# MCU.net
KiCad netlist of a schematic drawn in Altium Designer
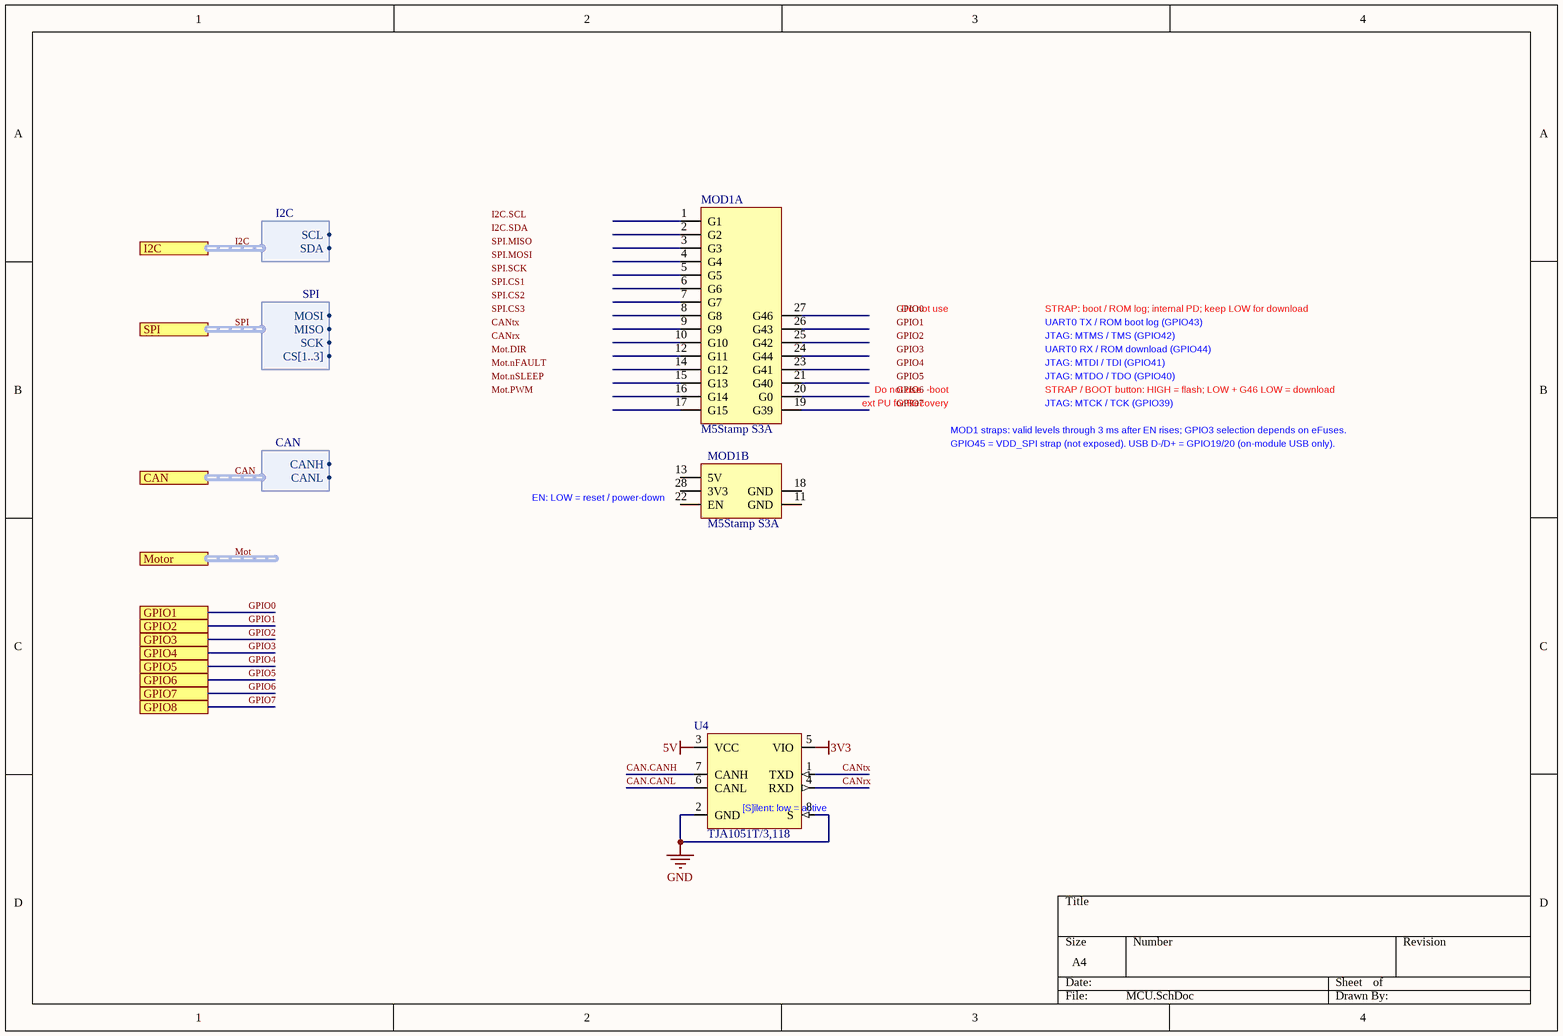
[diagram p0: MCU.SchDoc]

(export (version "E")
  (design (tool "Eeschema 10.0.6"))
  (components
    (comp (ref "MOD1")
      (value "M5Stamp S3A")
      (footprint "M5Stamp S3A-mfg")
      (description "ESP32-S3FN8, 8MB Flash, RGB LED")
      (libsource (lib "AFR365") (part "M5Stamp_S3A"))
    )
    (comp (ref "U4")
      (value "TJA1051T/3,118")
      (footprint "NXP-SOIC-8_L")
      (description "Interface Circuit, 1-Trnsvr, PDSO8")
      (libsource (lib "AFR365") (part "NXP-TJA1051T_3-SOIC-8"))
    )
  )
  (nets
    (net (code "5") (name "/CAN.CANH") (class "Default")
      (node (ref "U4") (pin "7") (pinfunction "CANH_7") (pintype "passive"))
    )
    (net (code "6") (name "/CAN.CANL") (class "Default")
      (node (ref "U4") (pin "6") (pinfunction "CANL_6") (pintype "passive"))
    )
    (net (code "7") (name "/CANrx") (class "Default")
      (node (ref "U4") (pin "4") (pinfunction "RXD_4") (pintype "output"))
    )
    (net (code "8") (name "/CANtx") (class "Default")
      (node (ref "U4") (pin "1") (pinfunction "TXD_1") (pintype "input"))
    )
    (net (code "26") (name "3V3") (class "Default")
      (node (ref "U4") (pin "5") (pinfunction "VIO_5") (pintype "power_in"))
    )
    (net (code "27") (name "5V") (class "Default")
      (node (ref "U4") (pin "3") (pinfunction "VCC_3") (pintype "power_in"))
    )
    (net (code "28") (name "GND") (class "Default")
      (node (ref "U4") (pin "2") (pinfunction "GND_2") (pintype "power_in"))
      (node (ref "U4") (pin "8") (pinfunction "S_8") (pintype "input"))
    )
    (net (code "29") (name "unconnected-(MOD1A-G0-Pad20)") (class "Default")
      (node (ref "MOD1") (pin "20") (pinfunction "G0_20") (pintype "passive"))
    )
    (net (code "30") (name "unconnected-(MOD1A-G1-Pad1)") (class "Default")
      (node (ref "MOD1") (pin "1") (pinfunction "G1_1") (pintype "passive"))
    )
    (net (code "31") (name "unconnected-(MOD1A-G2-Pad2)") (class "Default")
      (node (ref "MOD1") (pin "2") (pinfunction "G2_2") (pintype "passive"))
    )
    (net (code "32") (name "unconnected-(MOD1A-G3-Pad3)") (class "Default")
      (node (ref "MOD1") (pin "3") (pinfunction "G3_3") (pintype "passive"))
    )
    (net (code "33") (name "unconnected-(MOD1A-G4-Pad4)") (class "Default")
      (node (ref "MOD1") (pin "4") (pinfunction "G4_4") (pintype "passive"))
    )
    (net (code "34") (name "unconnected-(MOD1A-G5-Pad5)") (class "Default")
      (node (ref "MOD1") (pin "5") (pinfunction "G5_5") (pintype "passive"))
    )
    (net (code "35") (name "unconnected-(MOD1A-G6-Pad6)") (class "Default")
      (node (ref "MOD1") (pin "6") (pinfunction "G6_6") (pintype "passive"))
    )
    (net (code "36") (name "unconnected-(MOD1A-G7-Pad7)") (class "Default")
      (node (ref "MOD1") (pin "7") (pinfunction "G7_7") (pintype "passive"))
    )
    (net (code "37") (name "unconnected-(MOD1A-G8-Pad8)") (class "Default")
      (node (ref "MOD1") (pin "8") (pinfunction "G8_8") (pintype "passive"))
    )
    (net (code "38") (name "unconnected-(MOD1A-G9-Pad9)") (class "Default")
      (node (ref "MOD1") (pin "9") (pinfunction "G9_9") (pintype "passive"))
    )
    (net (code "39") (name "unconnected-(MOD1A-G10-Pad10)") (class "Default")
      (node (ref "MOD1") (pin "10") (pinfunction "G10_10") (pintype "passive"))
    )
    (net (code "40") (name "unconnected-(MOD1A-G11-Pad12)") (class "Default")
      (node (ref "MOD1") (pin "12") (pinfunction "G11_12") (pintype "passive"))
    )
    (net (code "41") (name "unconnected-(MOD1A-G12-Pad14)") (class "Default")
      (node (ref "MOD1") (pin "14") (pinfunction "G12_14") (pintype "passive"))
    )
    (net (code "42") (name "unconnected-(MOD1A-G13-Pad15)") (class "Default")
      (node (ref "MOD1") (pin "15") (pinfunction "G13_15") (pintype "passive"))
    )
    (net (code "43") (name "unconnected-(MOD1A-G14-Pad16)") (class "Default")
      (node (ref "MOD1") (pin "16") (pinfunction "G14_16") (pintype "passive"))
    )
    (net (code "44") (name "unconnected-(MOD1A-G15-Pad17)") (class "Default")
      (node (ref "MOD1") (pin "17") (pinfunction "G15_17") (pintype "passive"))
    )
    (net (code "45") (name "unconnected-(MOD1A-G39-Pad19)") (class "Default")
      (node (ref "MOD1") (pin "19") (pinfunction "G39_19") (pintype "passive"))
    )
    (net (code "46") (name "unconnected-(MOD1A-G40-Pad21)") (class "Default")
      (node (ref "MOD1") (pin "21") (pinfunction "G40_21") (pintype "passive"))
    )
    (net (code "47") (name "unconnected-(MOD1A-G41-Pad23)") (class "Default")
      (node (ref "MOD1") (pin "23") (pinfunction "G41_23") (pintype "passive"))
    )
    (net (code "48") (name "unconnected-(MOD1A-G42-Pad25)") (class "Default")
      (node (ref "MOD1") (pin "25") (pinfunction "G42_25") (pintype "passive"))
    )
    (net (code "49") (name "unconnected-(MOD1A-G43-Pad26)") (class "Default")
      (node (ref "MOD1") (pin "26") (pinfunction "G43_26") (pintype "passive"))
    )
    (net (code "50") (name "unconnected-(MOD1A-G44-Pad24)") (class "Default")
      (node (ref "MOD1") (pin "24") (pinfunction "G44_24") (pintype "passive"))
    )
    (net (code "51") (name "unconnected-(MOD1A-G46-Pad27)") (class "Default")
      (node (ref "MOD1") (pin "27") (pinfunction "G46_27") (pintype "passive"))
    )
    (net (code "52") (name "unconnected-(MOD1B-3V3-Pad28)") (class "Default")
      (node (ref "MOD1") (pin "28") (pinfunction "3V3_28") (pintype "passive"))
    )
    (net (code "53") (name "unconnected-(MOD1B-5V-Pad13)") (class "Default")
      (node (ref "MOD1") (pin "13") (pinfunction "5V_13") (pintype "passive"))
    )
    (net (code "54") (name "unconnected-(MOD1B-EN-Pad22)") (class "Default")
      (node (ref "MOD1") (pin "22") (pinfunction "EN_22") (pintype "passive"))
    )
    (net (code "55") (name "unconnected-(MOD1B-GND-Pad11)") (class "Default")
      (node (ref "MOD1") (pin "11") (pinfunction "GND_11") (pintype "passive"))
    )
    (net (code "56") (name "unconnected-(MOD1B-GND-Pad18)") (class "Default")
      (node (ref "MOD1") (pin "18") (pinfunction "GND_18") (pintype "passive"))
    )
  )
)
